# Comms_Cape.net
KiCad netlist of a schematic drawn in EAGLE
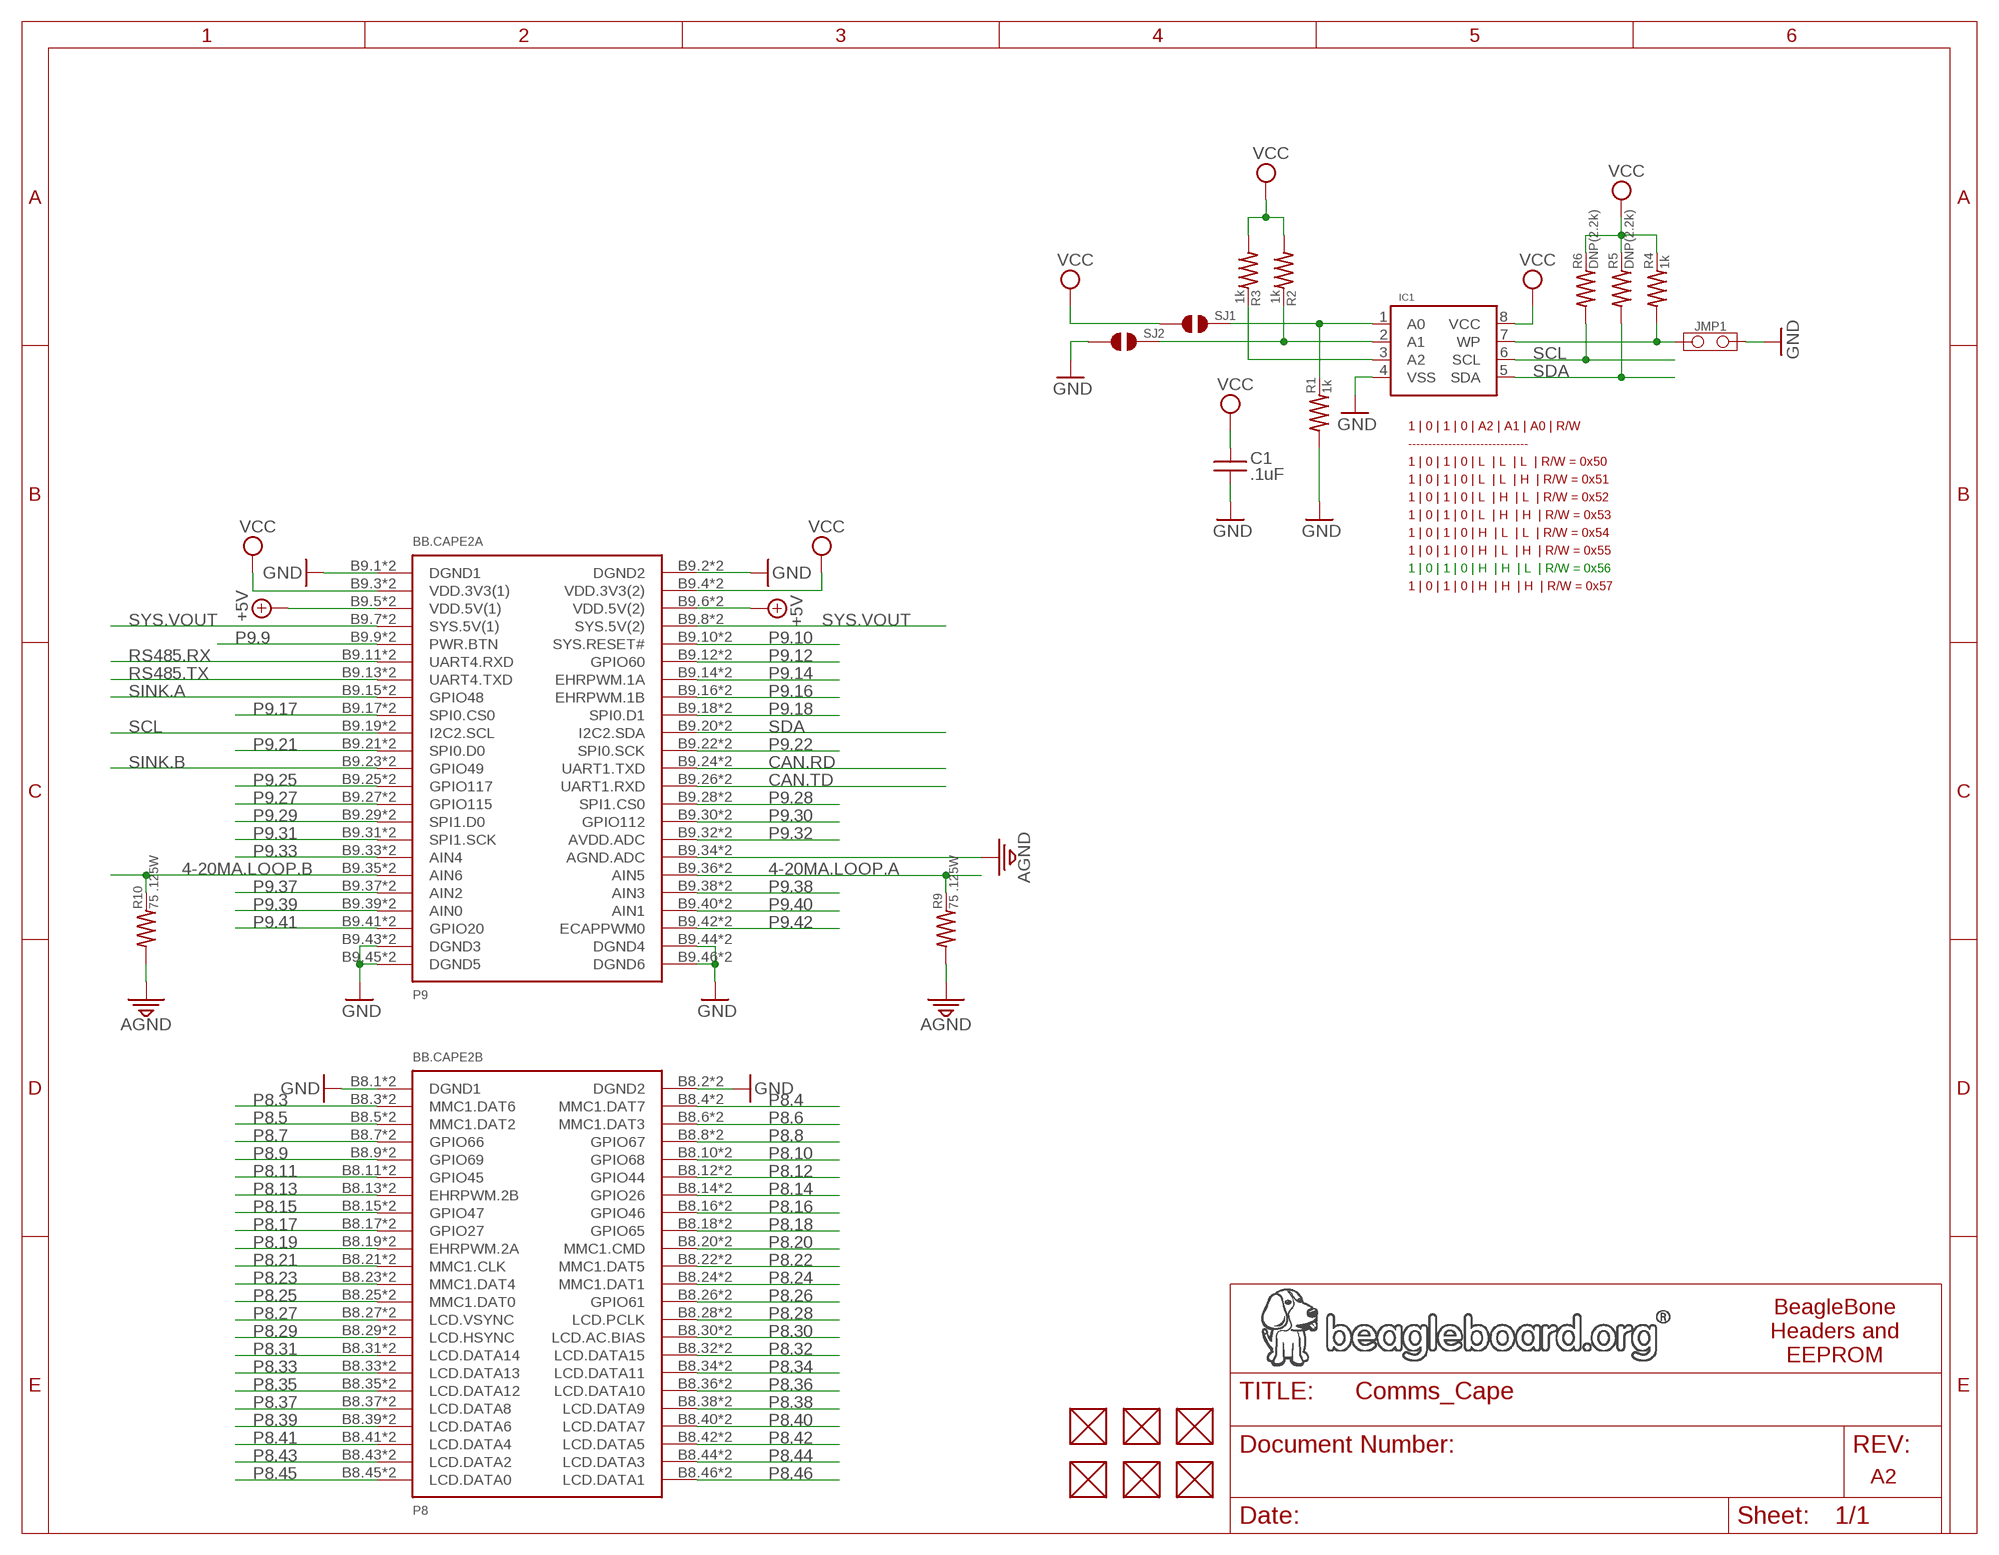
[diagram p0: schematic, sheet 1, part 1 of 2]
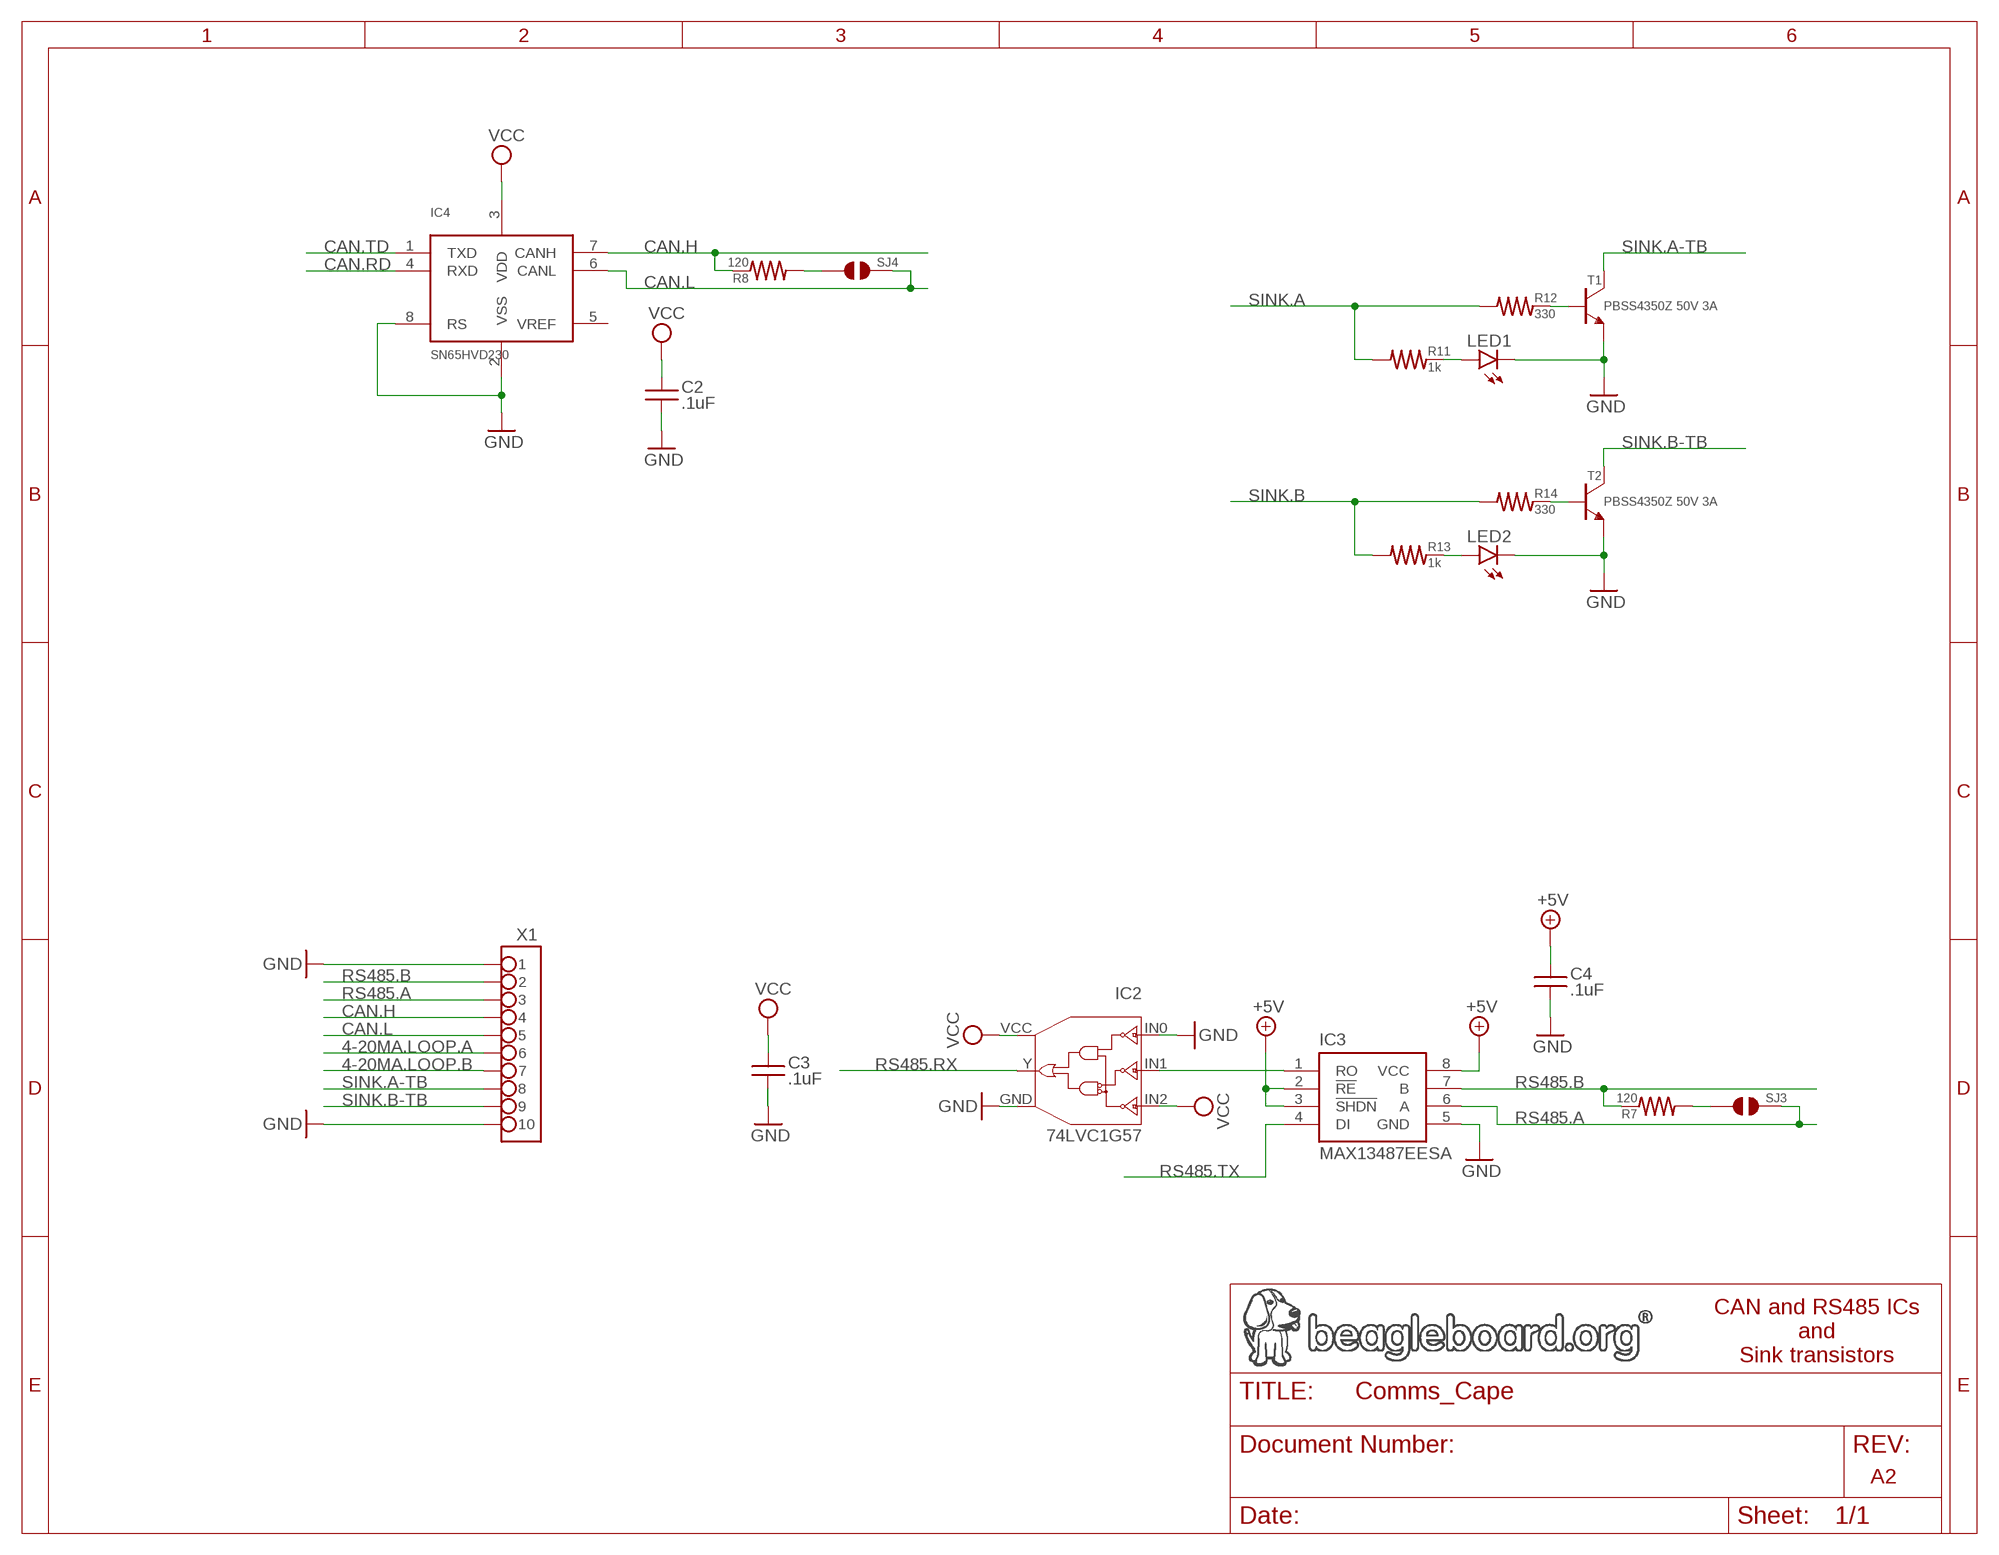
[diagram p1: schematic, sheet 1, part 2 of 2]

(export (version "E")
  (design (tool "Eeschema 10.0.6"))
  (components
    (comp (ref "BB.CAPE2")
      (value "BEAGLEBONE.CAPE.TOP/BOTTOM-PADS")
      (footprint "eagle-import:BEAGLEBONE.CAPE.TOP_BOTTOM-PADS")
      (libsource (lib "eagle-import") (part "BEAGLEBONE.CAPE.TOP/BOTTOM-PADS"))
    )
    (comp (ref "C1")
      (value ".1uF")
      (footprint "eagle-import:0402")
      (libsource (lib "eagle-import") (part "CAPACITOR-(INCH)-0402"))
    )
    (comp (ref "C2")
      (value ".1uF")
      (footprint "eagle-import:0402")
      (libsource (lib "eagle-import") (part "CAPACITOR-(INCH)-0402"))
    )
    (comp (ref "C3")
      (value ".1uF")
      (footprint "eagle-import:0402")
      (libsource (lib "eagle-import") (part "CAPACITOR-(INCH)-0402"))
    )
    (comp (ref "C4")
      (value ".1uF")
      (footprint "eagle-import:0402")
      (libsource (lib "eagle-import") (part "CAPACITOR-(INCH)-0402"))
    )
    (comp (ref "FUD1")
      (value "FIDUCIAL")
      (footprint "eagle-import:FIDUCIAL_40MIL")
      (libsource (lib "eagle-import") (part "FIDUCIAL"))
    )
    (comp (ref "FUD2")
      (value "FIDUCIAL")
      (footprint "eagle-import:FIDUCIAL_40MIL")
      (libsource (lib "eagle-import") (part "FIDUCIAL"))
    )
    (comp (ref "FUD3")
      (value "FIDUCIAL")
      (footprint "eagle-import:FIDUCIAL_40MIL")
      (libsource (lib "eagle-import") (part "FIDUCIAL"))
    )
    (comp (ref "FUD4")
      (value "FIDUCIAL")
      (footprint "eagle-import:FIDUCIAL_40MIL")
      (libsource (lib "eagle-import") (part "FIDUCIAL"))
    )
    (comp (ref "FUD5")
      (value "FIDUCIAL")
      (footprint "eagle-import:FIDUCIAL_40MIL")
      (libsource (lib "eagle-import") (part "FIDUCIAL"))
    )
    (comp (ref "FUD6")
      (value "FIDUCIAL")
      (footprint "eagle-import:FIDUCIAL_40MIL")
      (libsource (lib "eagle-import") (part "FIDUCIAL"))
    )
    (comp (ref "IC1")
      (value "CAT24C32")
      (footprint "eagle-import:UDFN8,2X3(ON-SEMI)")
      (libsource (lib "eagle-import") (part "CAT24C32"))
    )
    (comp (ref "IC2")
      (value "74LVC1G57")
      (footprint "eagle-import:SOT-23-6")
      (libsource (lib "eagle-import") (part "1G57-SOT-23-6"))
    )
    (comp (ref "IC3")
      (value "MAX13487EESA")
      (footprint "eagle-import:SOIC8")
      (libsource (lib "eagle-import") (part "MAX13487EESA"))
    )
    (comp (ref "IC4")
      (value "SN65HVD230")
      (footprint "eagle-import:SO8")
      (libsource (lib "eagle-import") (part "MCP2551"))
    )
    (comp (ref "JMP1")
      (value "JUMPER-(X2)")
      (footprint "eagle-import:JUMPER-(X2)")
      (libsource (lib "eagle-import") (part "JUMPER-(X2)"))
    )
    (comp (ref "LED1")
      (value "LED-(INCH)-0805")
      (footprint "eagle-import:0805-LED")
      (libsource (lib "eagle-import") (part "LED-(INCH)-0805"))
    )
    (comp (ref "LED2")
      (value "LED-(INCH)-0805")
      (footprint "eagle-import:0805-LED")
      (libsource (lib "eagle-import") (part "LED-(INCH)-0805"))
    )
    (comp (ref "R1")
      (value "1k")
      (footprint "eagle-import:0402")
      (libsource (lib "eagle-import") (part "RESISTOR-(INCH)-0402"))
    )
    (comp (ref "R2")
      (value "1k")
      (footprint "eagle-import:0402")
      (libsource (lib "eagle-import") (part "RESISTOR-(INCH)-0402"))
    )
    (comp (ref "R3")
      (value "1k")
      (footprint "eagle-import:0402")
      (libsource (lib "eagle-import") (part "RESISTOR-(INCH)-0402"))
    )
    (comp (ref "R4")
      (value "1k")
      (footprint "eagle-import:0402")
      (libsource (lib "eagle-import") (part "RESISTOR-(INCH)-0402"))
    )
    (comp (ref "R5")
      (value "DNP(2.2k)")
      (footprint "eagle-import:0402")
      (libsource (lib "eagle-import") (part "RESISTOR-(INCH)-0402"))
    )
    (comp (ref "R6")
      (value "DNP(2.2k)")
      (footprint "eagle-import:0402")
      (libsource (lib "eagle-import") (part "RESISTOR-(INCH)-0402"))
    )
    (comp (ref "R7")
      (value "120")
      (footprint "eagle-import:0402")
      (libsource (lib "eagle-import") (part "RESISTOR-(INCH)-0402"))
    )
    (comp (ref "R8")
      (value "120")
      (footprint "eagle-import:0402")
      (libsource (lib "eagle-import") (part "RESISTOR-(INCH)-0402"))
    )
    (comp (ref "R9")
      (value "75 .125W")
      (footprint "eagle-import:0805")
      (libsource (lib "eagle-import") (part "RESISTOR-(INCH)-0805"))
    )
    (comp (ref "R10")
      (value "75 .125W")
      (footprint "eagle-import:0805")
      (libsource (lib "eagle-import") (part "RESISTOR-(INCH)-0805"))
    )
    (comp (ref "R11")
      (value "1k")
      (footprint "eagle-import:0402")
      (libsource (lib "eagle-import") (part "RESISTOR-(INCH)-0402"))
    )
    (comp (ref "R12")
      (value "330")
      (footprint "eagle-import:0402")
      (libsource (lib "eagle-import") (part "RESISTOR-(INCH)-0402"))
    )
    (comp (ref "R13")
      (value "1k")
      (footprint "eagle-import:0402")
      (libsource (lib "eagle-import") (part "RESISTOR-(INCH)-0402"))
    )
    (comp (ref "R14")
      (value "330")
      (footprint "eagle-import:0402")
      (libsource (lib "eagle-import") (part "RESISTOR-(INCH)-0402"))
    )
    (comp (ref "SJ1")
      (value "SOLDER.JOINT-(INCH)-0402")
      (footprint "eagle-import:SOLDER.JOINT(0402)")
      (libsource (lib "eagle-import") (part "SOLDER.JOINT-(INCH)-0402"))
    )
    (comp (ref "SJ2")
      (value "SOLDER.JOINT-(INCH)-0402")
      (footprint "eagle-import:SOLDER.JOINT(0402)")
      (libsource (lib "eagle-import") (part "SOLDER.JOINT-(INCH)-0402"))
    )
    (comp (ref "SJ3")
      (value "SOLDER.JOINT-(INCH)-0402")
      (footprint "eagle-import:SOLDER.JOINT(0402)")
      (libsource (lib "eagle-import") (part "SOLDER.JOINT-(INCH)-0402"))
    )
    (comp (ref "SJ4")
      (value "SOLDER.JOINT-(INCH)-0402")
      (footprint "eagle-import:SOLDER.JOINT(0402)")
      (libsource (lib "eagle-import") (part "SOLDER.JOINT-(INCH)-0402"))
    )
    (comp (ref "T1")
      (value "PBSS4350Z 50V 3A")
      (footprint "eagle-import:SOT223")
      (libsource (lib "eagle-import") (part "PBSS4350Z"))
    )
    (comp (ref "T2")
      (value "PBSS4350Z 50V 3A")
      (footprint "eagle-import:SOT223")
      (libsource (lib "eagle-import") (part "PBSS4350Z"))
    )
    (comp (ref "X1")
      (value "TB-10TERM-150MIL.PITCH")
      (footprint "eagle-import:TERMINAL.BLOCK-10TERM-150MIL.PITCH")
      (libsource (lib "eagle-import") (part "TB-10TERM-150MIL.PITCH"))
    )
  )
  (nets
    (net (code "1") (name "+5V") (class "Default")
      (node (ref "BB.CAPE2") (pin "B9.5") (pinfunction "VDD.5V(1)_B9.5") (pintype "bidirectional"))
      (node (ref "BB.CAPE2") (pin "B9.6") (pinfunction "VDD.5V(2)_B9.6") (pintype "bidirectional"))
      (node (ref "BB.CAPE2") (pin "T9.5") (pinfunction "VDD.5V(1)_T9.5") (pintype "bidirectional"))
      (node (ref "BB.CAPE2") (pin "T9.6") (pinfunction "VDD.5V(2)_T9.6") (pintype "bidirectional"))
      (node (ref "C4") (pin "1") (pinfunction "1_1") (pintype "bidirectional"))
      (node (ref "IC3") (pin "2") (pinfunction "~{RE}_2") (pintype "input"))
      (node (ref "IC3") (pin "3") (pinfunction "~{SHDN}_3") (pintype "input"))
      (node (ref "IC3") (pin "8") (pinfunction "VCC_8") (pintype "power_in"))
    )
    (net (code "2") (name "/4-20MA.LOOP.A") (class "Default")
      (node (ref "BB.CAPE2") (pin "B9.36") (pinfunction "AIN5_B9.36") (pintype "bidirectional"))
      (node (ref "BB.CAPE2") (pin "T9.36") (pinfunction "AIN5_T9.36") (pintype "bidirectional"))
      (node (ref "R9") (pin "2") (pinfunction "2_2") (pintype "bidirectional"))
      (node (ref "X1") (pin "6") (pinfunction "6_6") (pintype "bidirectional"))
    )
    (net (code "3") (name "/4-20MA.LOOP.B") (class "Default")
      (node (ref "BB.CAPE2") (pin "B9.35") (pinfunction "AIN6_B9.35") (pintype "bidirectional"))
      (node (ref "BB.CAPE2") (pin "T9.35") (pinfunction "AIN6_T9.35") (pintype "bidirectional"))
      (node (ref "R10") (pin "2") (pinfunction "2_2") (pintype "bidirectional"))
      (node (ref "X1") (pin "7") (pinfunction "7_7") (pintype "bidirectional"))
    )
    (net (code "4") (name "/CAN.H") (class "Default")
      (node (ref "IC4") (pin "7") (pinfunction "CANH_7") (pintype "bidirectional"))
      (node (ref "R8") (pin "2") (pinfunction "2_2") (pintype "bidirectional"))
      (node (ref "X1") (pin "4") (pinfunction "4_4") (pintype "bidirectional"))
    )
    (net (code "5") (name "/CAN.L") (class "Default")
      (node (ref "IC4") (pin "6") (pinfunction "CANL_6") (pintype "bidirectional"))
      (node (ref "SJ4") (pin "2") (pinfunction "2_2") (pintype "bidirectional"))
      (node (ref "X1") (pin "5") (pinfunction "5_5") (pintype "bidirectional"))
    )
    (net (code "6") (name "/CAN.RD") (class "Default")
      (node (ref "BB.CAPE2") (pin "B9.24") (pinfunction "UART1.TXD_B9.24") (pintype "bidirectional"))
      (node (ref "BB.CAPE2") (pin "T9.24") (pinfunction "UART1.TXD_T9.24") (pintype "bidirectional"))
      (node (ref "IC4") (pin "4") (pinfunction "RXD_4") (pintype "bidirectional"))
    )
    (net (code "7") (name "/CAN.TD") (class "Default")
      (node (ref "BB.CAPE2") (pin "B9.26") (pinfunction "UART1.RXD_B9.26") (pintype "bidirectional"))
      (node (ref "BB.CAPE2") (pin "T9.26") (pinfunction "UART1.RXD_T9.26") (pintype "bidirectional"))
      (node (ref "IC4") (pin "1") (pinfunction "TXD_1") (pintype "bidirectional"))
    )
    (net (code "8") (name "/P8.3") (class "Default")
      (node (ref "BB.CAPE2") (pin "B8.3") (pinfunction "MMC1.DAT6_B8.3") (pintype "bidirectional"))
      (node (ref "BB.CAPE2") (pin "T8.3") (pinfunction "MMC1.DAT6_T8.3") (pintype "bidirectional"))
    )
    (net (code "9") (name "/P8.4") (class "Default")
      (node (ref "BB.CAPE2") (pin "B8.4") (pinfunction "MMC1.DAT7_B8.4") (pintype "bidirectional"))
      (node (ref "BB.CAPE2") (pin "T8.4") (pinfunction "MMC1.DAT7_T8.4") (pintype "bidirectional"))
    )
    (net (code "10") (name "/P8.5") (class "Default")
      (node (ref "BB.CAPE2") (pin "B8.5") (pinfunction "MMC1.DAT2_B8.5") (pintype "bidirectional"))
      (node (ref "BB.CAPE2") (pin "T8.5") (pinfunction "MMC1.DAT2_T8.5") (pintype "bidirectional"))
    )
    (net (code "11") (name "/P8.6") (class "Default")
      (node (ref "BB.CAPE2") (pin "B8.6") (pinfunction "MMC1.DAT3_B8.6") (pintype "bidirectional"))
      (node (ref "BB.CAPE2") (pin "T8.6") (pinfunction "MMC1.DAT3_T8.6") (pintype "bidirectional"))
    )
    (net (code "12") (name "/P8.7") (class "Default")
      (node (ref "BB.CAPE2") (pin "B8.7") (pinfunction "GPIO66_B8.7") (pintype "bidirectional"))
      (node (ref "BB.CAPE2") (pin "T8.7") (pinfunction "GPIO66_T8.7") (pintype "bidirectional"))
    )
    (net (code "13") (name "/P8.8") (class "Default")
      (node (ref "BB.CAPE2") (pin "B8.8") (pinfunction "GPIO67_B8.8") (pintype "bidirectional"))
      (node (ref "BB.CAPE2") (pin "T8.8") (pinfunction "GPIO67_T8.8") (pintype "bidirectional"))
    )
    (net (code "14") (name "/P8.9") (class "Default")
      (node (ref "BB.CAPE2") (pin "B8.9") (pinfunction "GPIO69_B8.9") (pintype "bidirectional"))
      (node (ref "BB.CAPE2") (pin "T8.9") (pinfunction "GPIO69_T8.9") (pintype "bidirectional"))
    )
    (net (code "15") (name "/P8.10") (class "Default")
      (node (ref "BB.CAPE2") (pin "B8.10") (pinfunction "GPIO68_B8.10") (pintype "bidirectional"))
      (node (ref "BB.CAPE2") (pin "T8.10") (pinfunction "GPIO68_T8.10") (pintype "bidirectional"))
    )
    (net (code "16") (name "/P8.11") (class "Default")
      (node (ref "BB.CAPE2") (pin "B8.11") (pinfunction "GPIO45_B8.11") (pintype "bidirectional"))
      (node (ref "BB.CAPE2") (pin "T8.11") (pinfunction "GPIO45_T8.11") (pintype "bidirectional"))
    )
    (net (code "17") (name "/P8.12") (class "Default")
      (node (ref "BB.CAPE2") (pin "B8.12") (pinfunction "GPIO44_B8.12") (pintype "bidirectional"))
      (node (ref "BB.CAPE2") (pin "T8.12") (pinfunction "GPIO44_T8.12") (pintype "bidirectional"))
    )
    (net (code "18") (name "/P8.13") (class "Default")
      (node (ref "BB.CAPE2") (pin "B8.13") (pinfunction "EHRPWM.2B_B8.13") (pintype "bidirectional"))
      (node (ref "BB.CAPE2") (pin "T8.13") (pinfunction "EHRPWM.2B_T8.13") (pintype "bidirectional"))
    )
    (net (code "19") (name "/P8.14") (class "Default")
      (node (ref "BB.CAPE2") (pin "B8.14") (pinfunction "GPIO26_B8.14") (pintype "bidirectional"))
      (node (ref "BB.CAPE2") (pin "T8.14") (pinfunction "GPIO26_T8.14") (pintype "bidirectional"))
    )
    (net (code "20") (name "/P8.15") (class "Default")
      (node (ref "BB.CAPE2") (pin "B8.15") (pinfunction "GPIO47_B8.15") (pintype "bidirectional"))
      (node (ref "BB.CAPE2") (pin "T8.15") (pinfunction "GPIO47_T8.15") (pintype "bidirectional"))
    )
    (net (code "21") (name "/P8.16") (class "Default")
      (node (ref "BB.CAPE2") (pin "B8.16") (pinfunction "GPIO46_B8.16") (pintype "bidirectional"))
      (node (ref "BB.CAPE2") (pin "T8.16") (pinfunction "GPIO46_T8.16") (pintype "bidirectional"))
    )
    (net (code "22") (name "/P8.17") (class "Default")
      (node (ref "BB.CAPE2") (pin "B8.17") (pinfunction "GPIO27_B8.17") (pintype "bidirectional"))
      (node (ref "BB.CAPE2") (pin "T8.17") (pinfunction "GPIO27_T8.17") (pintype "bidirectional"))
    )
    (net (code "23") (name "/P8.18") (class "Default")
      (node (ref "BB.CAPE2") (pin "B8.18") (pinfunction "GPIO65_B8.18") (pintype "bidirectional"))
      (node (ref "BB.CAPE2") (pin "T8.18") (pinfunction "GPIO65_T8.18") (pintype "bidirectional"))
    )
    (net (code "24") (name "/P8.19") (class "Default")
      (node (ref "BB.CAPE2") (pin "B8.19") (pinfunction "EHRPWM.2A_B8.19") (pintype "bidirectional"))
      (node (ref "BB.CAPE2") (pin "T8.19") (pinfunction "EHRPWM.2A_T8.19") (pintype "bidirectional"))
    )
    (net (code "25") (name "/P8.20") (class "Default")
      (node (ref "BB.CAPE2") (pin "B8.20") (pinfunction "MMC1.CMD_B8.20") (pintype "bidirectional"))
      (node (ref "BB.CAPE2") (pin "T8.20") (pinfunction "MMC1.CMD_T8.20") (pintype "bidirectional"))
    )
    (net (code "26") (name "/P8.21") (class "Default")
      (node (ref "BB.CAPE2") (pin "B8.21") (pinfunction "MMC1.CLK_B8.21") (pintype "bidirectional"))
      (node (ref "BB.CAPE2") (pin "T8.21") (pinfunction "MMC1.CLK_T8.21") (pintype "bidirectional"))
    )
    (net (code "27") (name "/P8.22") (class "Default")
      (node (ref "BB.CAPE2") (pin "B8.22") (pinfunction "MMC1.DAT5_B8.22") (pintype "bidirectional"))
      (node (ref "BB.CAPE2") (pin "T8.22") (pinfunction "MMC1.DAT5_T8.22") (pintype "bidirectional"))
    )
    (net (code "28") (name "/P8.23") (class "Default")
      (node (ref "BB.CAPE2") (pin "B8.23") (pinfunction "MMC1.DAT4_B8.23") (pintype "bidirectional"))
      (node (ref "BB.CAPE2") (pin "T8.23") (pinfunction "MMC1.DAT4_T8.23") (pintype "bidirectional"))
    )
    (net (code "29") (name "/P8.24") (class "Default")
      (node (ref "BB.CAPE2") (pin "B8.24") (pinfunction "MMC1.DAT1_B8.24") (pintype "bidirectional"))
      (node (ref "BB.CAPE2") (pin "T8.24") (pinfunction "MMC1.DAT1_T8.24") (pintype "bidirectional"))
    )
    (net (code "30") (name "/P8.25") (class "Default")
      (node (ref "BB.CAPE2") (pin "B8.25") (pinfunction "MMC1.DAT0_B8.25") (pintype "bidirectional"))
      (node (ref "BB.CAPE2") (pin "T8.25") (pinfunction "MMC1.DAT0_T8.25") (pintype "bidirectional"))
    )
    (net (code "31") (name "/P8.26") (class "Default")
      (node (ref "BB.CAPE2") (pin "B8.26") (pinfunction "GPIO61_B8.26") (pintype "bidirectional"))
      (node (ref "BB.CAPE2") (pin "T8.26") (pinfunction "GPIO61_T8.26") (pintype "bidirectional"))
    )
    (net (code "32") (name "/P8.27") (class "Default")
      (node (ref "BB.CAPE2") (pin "B8.27") (pinfunction "LCD.VSYNC_B8.27") (pintype "bidirectional"))
      (node (ref "BB.CAPE2") (pin "T8.27") (pinfunction "LCD.VSYNC_T8.27") (pintype "bidirectional"))
    )
    (net (code "33") (name "/P8.28") (class "Default")
      (node (ref "BB.CAPE2") (pin "B8.28") (pinfunction "LCD.PCLK_B8.28") (pintype "bidirectional"))
      (node (ref "BB.CAPE2") (pin "T8.28") (pinfunction "LCD.PCLK_T8.28") (pintype "bidirectional"))
    )
    (net (code "34") (name "/P8.29") (class "Default")
      (node (ref "BB.CAPE2") (pin "B8.29") (pinfunction "LCD.HSYNC_B8.29") (pintype "bidirectional"))
      (node (ref "BB.CAPE2") (pin "T8.29") (pinfunction "LCD.HSYNC_T8.29") (pintype "bidirectional"))
    )
    (net (code "35") (name "/P8.30") (class "Default")
      (node (ref "BB.CAPE2") (pin "B8.30") (pinfunction "LCD.AC.BIAS_B8.30") (pintype "bidirectional"))
      (node (ref "BB.CAPE2") (pin "T8.30") (pinfunction "LCD.AC.BIAS_T8.30") (pintype "bidirectional"))
    )
    (net (code "36") (name "/P8.31") (class "Default")
      (node (ref "BB.CAPE2") (pin "B8.31") (pinfunction "LCD.DATA14_B8.31") (pintype "bidirectional"))
      (node (ref "BB.CAPE2") (pin "T8.31") (pinfunction "LCD.DATA14_T8.31") (pintype "bidirectional"))
    )
    (net (code "37") (name "/P8.32") (class "Default")
      (node (ref "BB.CAPE2") (pin "B8.32") (pinfunction "LCD.DATA15_B8.32") (pintype "bidirectional"))
      (node (ref "BB.CAPE2") (pin "T8.32") (pinfunction "LCD.DATA15_T8.32") (pintype "bidirectional"))
    )
    (net (code "38") (name "/P8.33") (class "Default")
      (node (ref "BB.CAPE2") (pin "B8.33") (pinfunction "LCD.DATA13_B8.33") (pintype "bidirectional"))
      (node (ref "BB.CAPE2") (pin "T8.33") (pinfunction "LCD.DATA13_T8.33") (pintype "bidirectional"))
    )
    (net (code "39") (name "/P8.34") (class "Default")
      (node (ref "BB.CAPE2") (pin "B8.34") (pinfunction "LCD.DATA11_B8.34") (pintype "bidirectional"))
      (node (ref "BB.CAPE2") (pin "T8.34") (pinfunction "LCD.DATA11_T8.34") (pintype "bidirectional"))
    )
    (net (code "40") (name "/P8.35") (class "Default")
      (node (ref "BB.CAPE2") (pin "B8.35") (pinfunction "LCD.DATA12_B8.35") (pintype "bidirectional"))
      (node (ref "BB.CAPE2") (pin "T8.35") (pinfunction "LCD.DATA12_T8.35") (pintype "bidirectional"))
    )
    (net (code "41") (name "/P8.36") (class "Default")
      (node (ref "BB.CAPE2") (pin "B8.36") (pinfunction "LCD.DATA10_B8.36") (pintype "bidirectional"))
      (node (ref "BB.CAPE2") (pin "T8.36") (pinfunction "LCD.DATA10_T8.36") (pintype "bidirectional"))
    )
    (net (code "42") (name "/P8.37") (class "Default")
      (node (ref "BB.CAPE2") (pin "B8.37") (pinfunction "LCD.DATA8_B8.37") (pintype "bidirectional"))
      (node (ref "BB.CAPE2") (pin "T8.37") (pinfunction "LCD.DATA8_T8.37") (pintype "bidirectional"))
    )
    (net (code "43") (name "/P8.38") (class "Default")
      (node (ref "BB.CAPE2") (pin "B8.38") (pinfunction "LCD.DATA9_B8.38") (pintype "bidirectional"))
      (node (ref "BB.CAPE2") (pin "T8.38") (pinfunction "LCD.DATA9_T8.38") (pintype "bidirectional"))
    )
    (net (code "44") (name "/P8.39") (class "Default")
      (node (ref "BB.CAPE2") (pin "B8.39") (pinfunction "LCD.DATA6_B8.39") (pintype "bidirectional"))
      (node (ref "BB.CAPE2") (pin "T8.39") (pinfunction "LCD.DATA6_T8.39") (pintype "bidirectional"))
    )
    (net (code "45") (name "/P8.40") (class "Default")
      (node (ref "BB.CAPE2") (pin "B8.40") (pinfunction "LCD.DATA7_B8.40") (pintype "bidirectional"))
      (node (ref "BB.CAPE2") (pin "T8.40") (pinfunction "LCD.DATA7_T8.40") (pintype "bidirectional"))
    )
    (net (code "46") (name "/P8.41") (class "Default")
      (node (ref "BB.CAPE2") (pin "B8.41") (pinfunction "LCD.DATA4_B8.41") (pintype "bidirectional"))
      (node (ref "BB.CAPE2") (pin "T8.41") (pinfunction "LCD.DATA4_T8.41") (pintype "bidirectional"))
    )
    (net (code "47") (name "/P8.42") (class "Default")
      (node (ref "BB.CAPE2") (pin "B8.42") (pinfunction "LCD.DATA5_B8.42") (pintype "bidirectional"))
      (node (ref "BB.CAPE2") (pin "T8.42") (pinfunction "LCD.DATA5_T8.42") (pintype "bidirectional"))
    )
    (net (code "48") (name "/P8.43") (class "Default")
      (node (ref "BB.CAPE2") (pin "B8.43") (pinfunction "LCD.DATA2_B8.43") (pintype "bidirectional"))
      (node (ref "BB.CAPE2") (pin "T8.43") (pinfunction "LCD.DATA2_T8.43") (pintype "bidirectional"))
    )
    (net (code "49") (name "/P8.44") (class "Default")
      (node (ref "BB.CAPE2") (pin "B8.44") (pinfunction "LCD.DATA3_B8.44") (pintype "bidirectional"))
      (node (ref "BB.CAPE2") (pin "T8.44") (pinfunction "LCD.DATA3_T8.44") (pintype "bidirectional"))
    )
    (net (code "50") (name "/P8.45") (class "Default")
      (node (ref "BB.CAPE2") (pin "B8.45") (pinfunction "LCD.DATA0_B8.45") (pintype "bidirectional"))
      (node (ref "BB.CAPE2") (pin "T8.45") (pinfunction "LCD.DATA0_T8.45") (pintype "bidirectional"))
    )
    (net (code "51") (name "/P8.46") (class "Default")
      (node (ref "BB.CAPE2") (pin "B8.46") (pinfunction "LCD.DATA1_B8.46") (pintype "bidirectional"))
      (node (ref "BB.CAPE2") (pin "T8.46") (pinfunction "LCD.DATA1_T8.46") (pintype "bidirectional"))
    )
    (net (code "52") (name "/P9.9") (class "Default")
      (node (ref "BB.CAPE2") (pin "B9.9") (pinfunction "PWR.BTN_B9.9") (pintype "bidirectional"))
      (node (ref "BB.CAPE2") (pin "T9.9") (pinfunction "PWR.BTN_T9.9") (pintype "bidirectional"))
    )
    (net (code "53") (name "/P9.10") (class "Default")
      (node (ref "BB.CAPE2") (pin "B9.10") (pinfunction "SYS.RESET#_B9.10") (pintype "bidirectional"))
      (node (ref "BB.CAPE2") (pin "T9.10") (pinfunction "SYS.RESET#_T9.10") (pintype "bidirectional"))
    )
    (net (code "54") (name "/P9.12") (class "Default")
      (node (ref "BB.CAPE2") (pin "B9.12") (pinfunction "GPIO60_B9.12") (pintype "bidirectional"))
      (node (ref "BB.CAPE2") (pin "T9.12") (pinfunction "GPIO60_T9.12") (pintype "bidirectional"))
    )
    (net (code "55") (name "/P9.14") (class "Default")
      (node (ref "BB.CAPE2") (pin "B9.14") (pinfunction "EHRPWM.1A_B9.14") (pintype "bidirectional"))
      (node (ref "BB.CAPE2") (pin "T9.14") (pinfunction "EHRPWM.1A_T9.14") (pintype "bidirectional"))
    )
    (net (code "56") (name "/P9.16") (class "Default")
      (node (ref "BB.CAPE2") (pin "B9.16") (pinfunction "EHRPWM.1B_B9.16") (pintype "bidirectional"))
      (node (ref "BB.CAPE2") (pin "T9.16") (pinfunction "EHRPWM.1B_T9.16") (pintype "bidirectional"))
    )
    (net (code "57") (name "/P9.17") (class "Default")
      (node (ref "BB.CAPE2") (pin "B9.17") (pinfunction "SPI0.CS0_B9.17") (pintype "bidirectional"))
      (node (ref "BB.CAPE2") (pin "T9.17") (pinfunction "SPI0.CS0_T9.17") (pintype "bidirectional"))
    )
    (net (code "58") (name "/P9.18") (class "Default")
      (node (ref "BB.CAPE2") (pin "B9.18") (pinfunction "SPI0.D1_B9.18") (pintype "bidirectional"))
      (node (ref "BB.CAPE2") (pin "T9.18") (pinfunction "SPI0.D1_T9.18") (pintype "bidirectional"))
    )
    (net (code "59") (name "/P9.21") (class "Default")
      (node (ref "BB.CAPE2") (pin "B9.21") (pinfunction "SPI0.D0_B9.21") (pintype "bidirectional"))
      (node (ref "BB.CAPE2") (pin "T9.21") (pinfunction "SPI0.D0_T9.21") (pintype "bidirectional"))
    )
    (net (code "60") (name "/P9.22") (class "Default")
      (node (ref "BB.CAPE2") (pin "B9.22") (pinfunction "SPI0.SCK_B9.22") (pintype "bidirectional"))
      (node (ref "BB.CAPE2") (pin "T9.22") (pinfunction "SPI0.SCK_T9.22") (pintype "bidirectional"))
    )
    (net (code "61") (name "/P9.25") (class "Default")
      (node (ref "BB.CAPE2") (pin "B9.25") (pinfunction "GPIO117_B9.25") (pintype "bidirectional"))
      (node (ref "BB.CAPE2") (pin "T9.25") (pinfunction "GPIO117_T9.25") (pintype "bidirectional"))
    )
    (net (code "62") (name "/P9.27") (class "Default")
      (node (ref "BB.CAPE2") (pin "B9.27") (pinfunction "GPIO115_B9.27") (pintype "bidirectional"))
      (node (ref "BB.CAPE2") (pin "T9.27") (pinfunction "GPIO115_T9.27") (pintype "bidirectional"))
    )
    (net (code "63") (name "/P9.28") (class "Default")
      (node (ref "BB.CAPE2") (pin "B9.28") (pinfunction "SPI1.CS0_B9.28") (pintype "bidirectional"))
      (node (ref "BB.CAPE2") (pin "T9.28") (pinfunction "SPI1.CS0_T9.28") (pintype "bidirectional"))
    )
    (net (code "64") (name "/P9.29") (class "Default")
      (node (ref "BB.CAPE2") (pin "B9.29") (pinfunction "SPI1.D0_B9.29") (pintype "bidirectional"))
      (node (ref "BB.CAPE2") (pin "T9.29") (pinfunction "SPI1.D0_T9.29") (pintype "bidirectional"))
    )
    (net (code "65") (name "/P9.30") (class "Default")
      (node (ref "BB.CAPE2") (pin "B9.30") (pinfunction "GPIO112_B9.30") (pintype "bidirectional"))
      (node (ref "BB.CAPE2") (pin "T9.30") (pinfunction "GPIO112_T9.30") (pintype "bidirectional"))
    )
    (net (code "66") (name "/P9.31") (class "Default")
      (node (ref "BB.CAPE2") (pin "B9.31") (pinfunction "SPI1.SCK_B9.31") (pintype "bidirectional"))
      (node (ref "BB.CAPE2") (pin "T9.31") (pinfunction "SPI1.SCK_T9.31") (pintype "bidirectional"))
    )
    (net (code "67") (name "/P9.32") (class "Default")
      (node (ref "BB.CAPE2") (pin "B9.32") (pinfunction "AVDD.ADC_B9.32") (pintype "bidirectional"))
      (node (ref "BB.CAPE2") (pin "T9.32") (pinfunction "AVDD.ADC_T9.32") (pintype "bidirectional"))
    )
    (net (code "68") (name "/P9.33") (class "Default")
      (node (ref "BB.CAPE2") (pin "B9.33") (pinfunction "AIN4_B9.33") (pintype "bidirectional"))
      (node (ref "BB.CAPE2") (pin "T9.33") (pinfunction "AIN4_T9.33") (pintype "bidirectional"))
    )
    (net (code "69") (name "/P9.37") (class "Default")
      (node (ref "BB.CAPE2") (pin "B9.37") (pinfunction "AIN2_B9.37") (pintype "bidirectional"))
      (node (ref "BB.CAPE2") (pin "T9.37") (pinfunction "AIN2_T9.37") (pintype "bidirectional"))
    )
    (net (code "70") (name "/P9.38") (class "Default")
      (node (ref "BB.CAPE2") (pin "B9.38") (pinfunction "AIN3_B9.38") (pintype "bidirectional"))
      (node (ref "BB.CAPE2") (pin "T9.38") (pinfunction "AIN3_T9.38") (pintype "bidirectional"))
    )
    (net (code "71") (name "/P9.39") (class "Default")
      (node (ref "BB.CAPE2") (pin "B9.39") (pinfunction "AIN0_B9.39") (pintype "bidirectional"))
      (node (ref "BB.CAPE2") (pin "T9.39") (pinfunction "AIN0_T9.39") (pintype "bidirectional"))
    )
    (net (code "72") (name "/P9.40") (class "Default")
      (node (ref "BB.CAPE2") (pin "B9.40") (pinfunction "AIN1_B9.40") (pintype "bidirectional"))
      (node (ref "BB.CAPE2") (pin "T9.40") (pinfunction "AIN1_T9.40") (pintype "bidirectional"))
    )
    (net (code "73") (name "/P9.41") (class "Default")
      (node (ref "BB.CAPE2") (pin "B9.41") (pinfunction "GPIO20_B9.41") (pintype "bidirectional"))
      (node (ref "BB.CAPE2") (pin "T9.41") (pinfunction "GPIO20_T9.41") (pintype "bidirectional"))
    )
    (net (code "74") (name "/P9.42") (class "Default")
      (node (ref "BB.CAPE2") (pin "B9.42") (pinfunction "ECAPPWM0_B9.42") (pintype "bidirectional"))
      (node (ref "BB.CAPE2") (pin "T9.42") (pinfunction "ECAPPWM0_T9.42") (pintype "bidirectional"))
    )
    (net (code "75") (name "/RS485.A") (class "Default")
      (node (ref "IC3") (pin "6") (pinfunction "A_6") (pintype "bidirectional"))
      (node (ref "SJ3") (pin "2") (pinfunction "2_2") (pintype "bidirectional"))
      (node (ref "X1") (pin "3") (pinfunction "3_3") (pintype "bidirectional"))
    )
    (net (code "76") (name "/RS485.B") (class "Default")
      (node (ref "IC3") (pin "7") (pinfunction "B_7") (pintype "bidirectional"))
      (node (ref "R7") (pin "2") (pinfunction "2_2") (pintype "bidirectional"))
      (node (ref "X1") (pin "2") (pinfunction "2_2") (pintype "bidirectional"))
    )
    (net (code "77") (name "/RS485.RX") (class "Default")
      (node (ref "BB.CAPE2") (pin "B9.11") (pinfunction "UART4.RXD_B9.11") (pintype "bidirectional"))
      (node (ref "BB.CAPE2") (pin "T9.11") (pinfunction "UART4.RXD_T9.11") (pintype "bidirectional"))
      (node (ref "IC2") (pin "Y") (pinfunction "Y_Y") (pintype "bidirectional"))
    )
    (net (code "78") (name "/RS485.TX") (class "Default")
      (node (ref "BB.CAPE2") (pin "B9.13") (pinfunction "UART4.TXD_B9.13") (pintype "bidirectional"))
      (node (ref "BB.CAPE2") (pin "T9.13") (pinfunction "UART4.TXD_T9.13") (pintype "bidirectional"))
      (node (ref "IC3") (pin "4") (pinfunction "DI_4") (pintype "input"))
    )
    (net (code "79") (name "/SCL") (class "Default")
      (node (ref "BB.CAPE2") (pin "B9.19") (pinfunction "I2C2.SCL_B9.19") (pintype "bidirectional"))
      (node (ref "BB.CAPE2") (pin "T9.19") (pinfunction "I2C2.SCL_T9.19") (pintype "bidirectional"))
      (node (ref "IC1") (pin "6") (pinfunction "SCL_6") (pintype "bidirectional"))
      (node (ref "R6") (pin "1") (pinfunction "1_1") (pintype "bidirectional"))
    )
    (net (code "80") (name "/SDA") (class "Default")
      (node (ref "BB.CAPE2") (pin "B9.20") (pinfunction "I2C2.SDA_B9.20") (pintype "bidirectional"))
      (node (ref "BB.CAPE2") (pin "T9.20") (pinfunction "I2C2.SDA_T9.20") (pintype "bidirectional"))
      (node (ref "IC1") (pin "5") (pinfunction "SDA_5") (pintype "bidirectional"))
      (node (ref "R5") (pin "1") (pinfunction "1_1") (pintype "bidirectional"))
    )
    (net (code "81") (name "/SINK.A") (class "Default")
      (node (ref "BB.CAPE2") (pin "B9.15") (pinfunction "GPIO48_B9.15") (pintype "bidirectional"))
      (node (ref "BB.CAPE2") (pin "T9.15") (pinfunction "GPIO48_T9.15") (pintype "bidirectional"))
      (node (ref "R11") (pin "1") (pinfunction "1_1") (pintype "bidirectional"))
      (node (ref "R12") (pin "1") (pinfunction "1_1") (pintype "bidirectional"))
    )
    (net (code "82") (name "/SINK.A-TB") (class "Default")
      (node (ref "T1") (pin "2") (pinfunction "C_2") (pintype "passive"))
      (node (ref "T1") (pin "4") (pinfunction "C_4") (pintype "passive"))
      (node (ref "X1") (pin "8") (pinfunction "8_8") (pintype "bidirectional"))
    )
    (net (code "83") (name "/SINK.B") (class "Default")
      (node (ref "BB.CAPE2") (pin "B9.23") (pinfunction "GPIO49_B9.23") (pintype "bidirectional"))
      (node (ref "BB.CAPE2") (pin "T9.23") (pinfunction "GPIO49_T9.23") (pintype "bidirectional"))
      (node (ref "R13") (pin "1") (pinfunction "1_1") (pintype "bidirectional"))
      (node (ref "R14") (pin "1") (pinfunction "1_1") (pintype "bidirectional"))
    )
    (net (code "84") (name "/SINK.B-TB") (class "Default")
      (node (ref "T2") (pin "2") (pinfunction "C_2") (pintype "passive"))
      (node (ref "T2") (pin "4") (pinfunction "C_4") (pintype "passive"))
      (node (ref "X1") (pin "9") (pinfunction "9_9") (pintype "bidirectional"))
    )
    (net (code "85") (name "/SYS.VOUT") (class "Default")
      (node (ref "BB.CAPE2") (pin "B9.7") (pinfunction "SYS.5V(1)_B9.7") (pintype "bidirectional"))
      (node (ref "BB.CAPE2") (pin "B9.8") (pinfunction "SYS.5V(2)_B9.8") (pintype "bidirectional"))
      (node (ref "BB.CAPE2") (pin "T9.7") (pinfunction "SYS.5V(1)_T9.7") (pintype "bidirectional"))
      (node (ref "BB.CAPE2") (pin "T9.8") (pinfunction "SYS.5V(2)_T9.8") (pintype "bidirectional"))
    )
    (net (code "86") (name "AGND") (class "Default")
      (node (ref "BB.CAPE2") (pin "B9.34") (pinfunction "AGND.ADC_B9.34") (pintype "bidirectional"))
      (node (ref "BB.CAPE2") (pin "T9.34") (pinfunction "AGND.ADC_T9.34") (pintype "bidirectional"))
      (node (ref "R10") (pin "1") (pinfunction "1_1") (pintype "bidirectional"))
      (node (ref "R9") (pin "1") (pinfunction "1_1") (pintype "bidirectional"))
    )
    (net (code "87") (name "GND") (class "Default")
      (node (ref "BB.CAPE2") (pin "B8.1") (pinfunction "DGND1_B8.1") (pintype "bidirectional"))
      (node (ref "BB.CAPE2") (pin "B8.2") (pinfunction "DGND2_B8.2") (pintype "bidirectional"))
      (node (ref "BB.CAPE2") (pin "B9.1") (pinfunction "DGND1_B9.1") (pintype "bidirectional"))
      (node (ref "BB.CAPE2") (pin "B9.2") (pinfunction "DGND2_B9.2") (pintype "bidirectional"))
      (node (ref "BB.CAPE2") (pin "B9.43") (pinfunction "DGND3_B9.43") (pintype "bidirectional"))
      (node (ref "BB.CAPE2") (pin "B9.44") (pinfunction "DGND4_B9.44") (pintype "bidirectional"))
      (node (ref "BB.CAPE2") (pin "B9.45") (pinfunction "DGND5_B9.45") (pintype "bidirectional"))
      (node (ref "BB.CAPE2") (pin "B9.46") (pinfunction "DGND6_B9.46") (pintype "bidirectional"))
      (node (ref "BB.CAPE2") (pin "T8.1") (pinfunction "DGND1_T8.1") (pintype "bidirectional"))
      (node (ref "BB.CAPE2") (pin "T8.2") (pinfunction "DGND2_T8.2") (pintype "bidirectional"))
      (node (ref "BB.CAPE2") (pin "T9.1") (pinfunction "DGND1_T9.1") (pintype "bidirectional"))
      (node (ref "BB.CAPE2") (pin "T9.2") (pinfunction "DGND2_T9.2") (pintype "bidirectional"))
      (node (ref "BB.CAPE2") (pin "T9.43") (pinfunction "DGND3_T9.43") (pintype "bidirectional"))
      (node (ref "BB.CAPE2") (pin "T9.44") (pinfunction "DGND4_T9.44") (pintype "bidirectional"))
      (node (ref "BB.CAPE2") (pin "T9.45") (pinfunction "DGND5_T9.45") (pintype "bidirectional"))
      (node (ref "BB.CAPE2") (pin "T9.46") (pinfunction "DGND6_T9.46") (pintype "bidirectional"))
      (node (ref "C1") (pin "2") (pinfunction "2_2") (pintype "bidirectional"))
      (node (ref "C2") (pin "2") (pinfunction "2_2") (pintype "bidirectional"))
      (node (ref "C3") (pin "2") (pinfunction "2_2") (pintype "bidirectional"))
      (node (ref "C4") (pin "2") (pinfunction "2_2") (pintype "bidirectional"))
      (node (ref "IC1") (pin "4") (pinfunction "VSS_4") (pintype "bidirectional"))
      (node (ref "IC2") (pin "GND") (pinfunction "GND_GND") (pintype "bidirectional"))
      (node (ref "IC2") (pin "IN0") (pinfunction "IN0_IN0") (pintype "bidirectional"))
      (node (ref "IC3") (pin "5") (pinfunction "GND_5") (pintype "power_in"))
      (node (ref "IC4") (pin "2") (pinfunction "VSS_2") (pintype "bidirectional"))
      (node (ref "IC4") (pin "8") (pinfunction "RS_8") (pintype "bidirectional"))
      (node (ref "JMP1") (pin "2") (pinfunction "2_2") (pintype "bidirectional"))
      (node (ref "LED1") (pin "K") (pinfunction "K_K") (pintype "passive"))
      (node (ref "LED2") (pin "K") (pinfunction "K_K") (pintype "passive"))
      (node (ref "R1") (pin "1") (pinfunction "1_1") (pintype "bidirectional"))
      (node (ref "SJ2") (pin "1") (pinfunction "1_1") (pintype "bidirectional"))
      (node (ref "T1") (pin "3") (pinfunction "E_3") (pintype "passive"))
      (node (ref "T2") (pin "3") (pinfunction "E_3") (pintype "passive"))
      (node (ref "X1") (pin "1") (pinfunction "1_1") (pintype "bidirectional"))
      (node (ref "X1") (pin "10") (pinfunction "10_10") (pintype "bidirectional"))
    )
    (net (code "88") (name "Net-(IC1-A0)") (class "Default")
      (node (ref "IC1") (pin "1") (pinfunction "A0_1") (pintype "bidirectional"))
      (node (ref "R1") (pin "2") (pinfunction "2_2") (pintype "bidirectional"))
      (node (ref "SJ1") (pin "2") (pinfunction "2_2") (pintype "bidirectional"))
    )
    (net (code "89") (name "Net-(IC1-A1)") (class "Default")
      (node (ref "IC1") (pin "2") (pinfunction "A1_2") (pintype "bidirectional"))
      (node (ref "R2") (pin "2") (pinfunction "2_2") (pintype "bidirectional"))
      (node (ref "SJ2") (pin "2") (pinfunction "2_2") (pintype "bidirectional"))
    )
    (net (code "90") (name "Net-(IC1-A2)") (class "Default")
      (node (ref "IC1") (pin "3") (pinfunction "A2_3") (pintype "bidirectional"))
      (node (ref "R3") (pin "2") (pinfunction "2_2") (pintype "bidirectional"))
    )
    (net (code "91") (name "Net-(IC1-WP)") (class "Default")
      (node (ref "IC1") (pin "7") (pinfunction "WP_7") (pintype "bidirectional"))
      (node (ref "JMP1") (pin "1") (pinfunction "1_1") (pintype "bidirectional"))
      (node (ref "R4") (pin "1") (pinfunction "1_1") (pintype "bidirectional"))
    )
    (net (code "92") (name "Net-(IC3-RO)") (class "Default")
      (node (ref "IC2") (pin "IN1") (pinfunction "IN1_IN1") (pintype "bidirectional"))
      (node (ref "IC3") (pin "1") (pinfunction "RO_1") (pintype "output"))
    )
    (net (code "93") (name "Net-(LED1-PadA)") (class "Default")
      (node (ref "LED1") (pin "A") (pinfunction "A_A") (pintype "passive"))
      (node (ref "R11") (pin "2") (pinfunction "2_2") (pintype "bidirectional"))
    )
    (net (code "94") (name "Net-(LED2-PadA)") (class "Default")
      (node (ref "LED2") (pin "A") (pinfunction "A_A") (pintype "passive"))
      (node (ref "R13") (pin "2") (pinfunction "2_2") (pintype "bidirectional"))
    )
    (net (code "95") (name "Net-(R7-Pad1)") (class "Default")
      (node (ref "R7") (pin "1") (pinfunction "1_1") (pintype "bidirectional"))
      (node (ref "SJ3") (pin "1") (pinfunction "1_1") (pintype "bidirectional"))
    )
    (net (code "96") (name "Net-(R8-Pad1)") (class "Default")
      (node (ref "R8") (pin "1") (pinfunction "1_1") (pintype "bidirectional"))
      (node (ref "SJ4") (pin "1") (pinfunction "1_1") (pintype "bidirectional"))
    )
    (net (code "97") (name "Net-(T1-B)") (class "Default")
      (node (ref "R12") (pin "2") (pinfunction "2_2") (pintype "bidirectional"))
      (node (ref "T1") (pin "1") (pinfunction "B_1") (pintype "passive"))
    )
    (net (code "98") (name "Net-(T2-B)") (class "Default")
      (node (ref "R14") (pin "2") (pinfunction "2_2") (pintype "bidirectional"))
      (node (ref "T2") (pin "1") (pinfunction "B_1") (pintype "passive"))
    )
    (net (code "99") (name "VCC") (class "Default")
      (node (ref "BB.CAPE2") (pin "B9.3") (pinfunction "VDD.3V3(1)_B9.3") (pintype "bidirectional"))
      (node (ref "BB.CAPE2") (pin "B9.4") (pinfunction "VDD.3V3(2)_B9.4") (pintype "bidirectional"))
      (node (ref "BB.CAPE2") (pin "T9.3") (pinfunction "VDD.3V3(1)_T9.3") (pintype "bidirectional"))
      (node (ref "BB.CAPE2") (pin "T9.4") (pinfunction "VDD.3V3(2)_T9.4") (pintype "bidirectional"))
      (node (ref "C1") (pin "1") (pinfunction "1_1") (pintype "bidirectional"))
      (node (ref "C2") (pin "1") (pinfunction "1_1") (pintype "bidirectional"))
      (node (ref "C3") (pin "1") (pinfunction "1_1") (pintype "bidirectional"))
      (node (ref "IC1") (pin "8") (pinfunction "VCC_8") (pintype "bidirectional"))
      (node (ref "IC2") (pin "IN2") (pinfunction "IN2_IN2") (pintype "bidirectional"))
      (node (ref "IC2") (pin "VCC") (pinfunction "VCC_VCC") (pintype "bidirectional"))
      (node (ref "IC4") (pin "3") (pinfunction "VDD_3") (pintype "bidirectional"))
      (node (ref "R2") (pin "1") (pinfunction "1_1") (pintype "bidirectional"))
      (node (ref "R3") (pin "1") (pinfunction "1_1") (pintype "bidirectional"))
      (node (ref "R4") (pin "2") (pinfunction "2_2") (pintype "bidirectional"))
      (node (ref "R5") (pin "2") (pinfunction "2_2") (pintype "bidirectional"))
      (node (ref "R6") (pin "2") (pinfunction "2_2") (pintype "bidirectional"))
      (node (ref "SJ1") (pin "1") (pinfunction "1_1") (pintype "bidirectional"))
    )
    (net (code "100") (name "unconnected-(FUD1-PadP$1)") (class "Default")
      (node (ref "FUD1") (pin "P$1") (pinfunction "P$1_P$1") (pintype "no_connect"))
    )
    (net (code "101") (name "unconnected-(FUD2-PadP$1)") (class "Default")
      (node (ref "FUD2") (pin "P$1") (pinfunction "P$1_P$1") (pintype "no_connect"))
    )
    (net (code "102") (name "unconnected-(FUD3-PadP$1)") (class "Default")
      (node (ref "FUD3") (pin "P$1") (pinfunction "P$1_P$1") (pintype "no_connect"))
    )
    (net (code "103") (name "unconnected-(FUD4-PadP$1)") (class "Default")
      (node (ref "FUD4") (pin "P$1") (pinfunction "P$1_P$1") (pintype "no_connect"))
    )
    (net (code "104") (name "unconnected-(FUD5-PadP$1)") (class "Default")
      (node (ref "FUD5") (pin "P$1") (pinfunction "P$1_P$1") (pintype "no_connect"))
    )
    (net (code "105") (name "unconnected-(FUD6-PadP$1)") (class "Default")
      (node (ref "FUD6") (pin "P$1") (pinfunction "P$1_P$1") (pintype "no_connect"))
    )
    (net (code "106") (name "unconnected-(IC4-VREF-Pad5)") (class "Default")
      (node (ref "IC4") (pin "5") (pinfunction "VREF_5") (pintype "bidirectional"))
    )
  )
)
